# OpenPLCv0_2_0_USBPortTypeA.net
KiCad netlist of a schematic drawn in Altium Designer
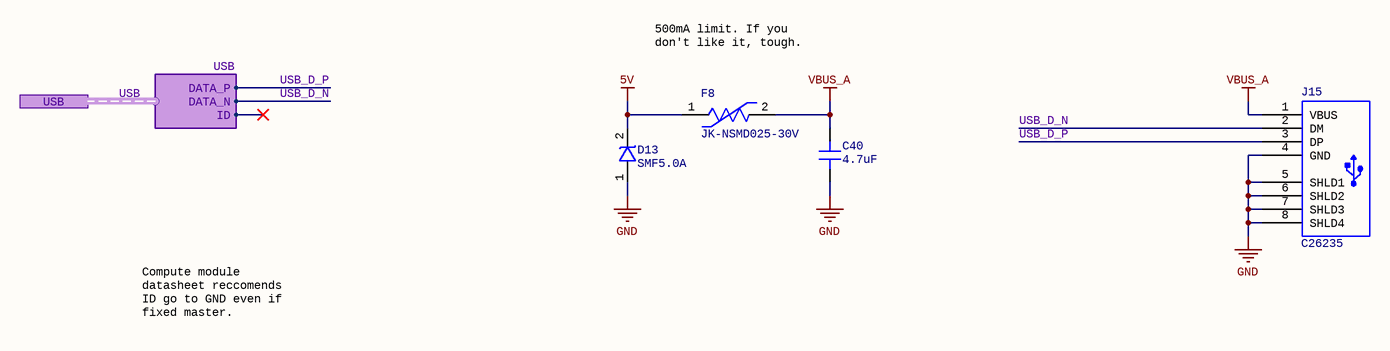
[diagram p0: OpenPLCv0.2.0_USBPortTypeA.SchDoc]

(export (version "E")
  (design (tool "Eeschema 10.0.6"))
  (components
    (comp (ref "C40")
      (value "CC0603KRX5R6BB475")
      (footprint "SMD_CAP_0603(0201)_N")
      (description "4.7uF ±10% 10V X5R 0603 Multilayer Ceramic Capacitors MLCC - SMD/SMT RoHS")
      (fields (field (name "TOLERANCE") "10%") (field (name "CAPACITANCE") "4.7uF"))
      (libsource (lib "BrauV2_Capacitor") (part "4.7uF 0603 10V 10%"))
    )
    (comp (ref "D13")
      (value "SMF5.0A")
      (footprint "SOD-123FL")
      (description "Unidirectional 5V 6.4V 9.2V 21.8A SMF(SOD123FL) TVS RoHS")
      (libsource (lib "BrauV2_Diode") (part "SMF5.0A"))
    )
    (comp (ref "F8")
      (value "JK-NSMD025-30V")
      (footprint "SMD_RES_1206(3216)_N")
      (description "Polymeric 30V 500mA 0.08s 700mΩ 1206 PTC Resettable Fuses RoHS")
      (libsource (lib "BrauV2_Resistor") (part "JK-NSMD025-30V"))
    )
    (comp (ref "J15")
      (value "C26235")
      (footprint "C26235")
      (description "USB - Type A Female USB 2 4 Through Hole USB Connectors RoHS")
      (libsource (lib "BrauV2_Connector") (part "C26235"))
    )
  )
  (nets
    (net (code "2") (name "/USB_D_N") (class "Default")
      (node (ref "J15") (pin "2") (pinfunction "DM_2") (pintype "passive"))
    )
    (net (code "3") (name "/USB_D_P") (class "Default")
      (node (ref "J15") (pin "3") (pinfunction "DP_3") (pintype "passive"))
    )
    (net (code "5") (name "5V") (class "Default")
      (node (ref "D13") (pin "2") (pinfunction "CATHODE_2") (pintype "passive"))
      (node (ref "F8") (pin "1") (pinfunction "1_1") (pintype "passive"))
    )
    (net (code "6") (name "GND") (class "Default")
      (node (ref "C40") (pin "1") (pinfunction "1_1") (pintype "passive"))
      (node (ref "D13") (pin "1") (pinfunction "ANODE_1") (pintype "passive"))
      (node (ref "J15") (pin "4") (pinfunction "GND_4") (pintype "passive"))
      (node (ref "J15") (pin "5") (pinfunction "SHLD1_5") (pintype "passive"))
      (node (ref "J15") (pin "6") (pinfunction "SHLD2_6") (pintype "passive"))
      (node (ref "J15") (pin "7") (pinfunction "SHLD3_7") (pintype "passive"))
      (node (ref "J15") (pin "8") (pinfunction "SHLD4_8") (pintype "passive"))
    )
    (net (code "7") (name "VBUS_A") (class "Default")
      (node (ref "C40") (pin "2") (pinfunction "2_2") (pintype "passive"))
      (node (ref "F8") (pin "2") (pinfunction "2_2") (pintype "passive"))
      (node (ref "J15") (pin "1") (pinfunction "VBUS_1") (pintype "passive"))
    )
  )
)
